# Revised.net
KiCad netlist of a schematic drawn in EAGLE
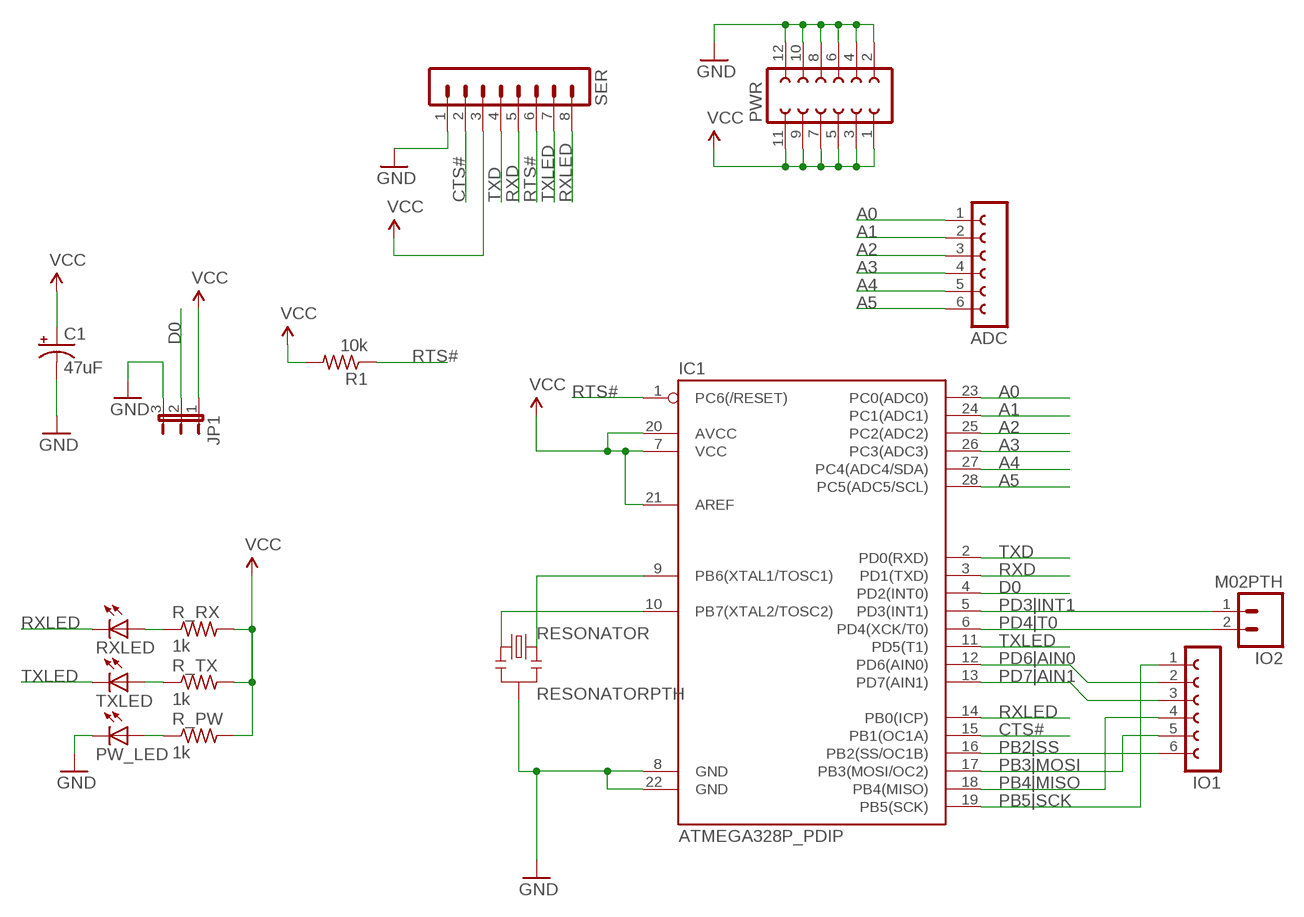
[diagram p0: schematic, sheet 1]

(export (version "E")
  (design (tool "Eeschema 10.0.6"))
  (components
    (comp (ref "ADC")
      (value "FE06-1")
      (footprint "eagle-import:FE06")
      (libsource (lib "eagle-import") (part "FE06-1"))
    )
    (comp (ref "C1")
      (value "47uF")
      (footprint "eagle-import:E2,5-6E")
      (libsource (lib "eagle-import") (part "CPOL-USE2,5-6E"))
    )
    (comp (ref "IC1")
      (value "ATMEGA328P_PDIP")
      (footprint "eagle-import:DIL28-3")
      (libsource (lib "eagle-import") (part "ATMEGA328P_PDIP"))
    )
    (comp (ref "IO1")
      (value "FE06-1")
      (footprint "eagle-import:FE06")
      (libsource (lib "eagle-import") (part "FE06-1"))
    )
    (comp (ref "IO2")
      (value "M02PTH")
      (footprint "eagle-import:1X02")
      (libsource (lib "eagle-import") (part "M02PTH"))
    )
    (comp (ref "JP1")
      (value "JP2E")
      (footprint "eagle-import:JP2")
      (libsource (lib "eagle-import") (part "JP2E"))
    )
    (comp (ref "PWR")
      (value "FE06-2")
      (footprint "eagle-import:FE06-2")
      (libsource (lib "eagle-import") (part "FE06-2"))
    )
    (comp (ref "PW_LED")
      (value "LED5MM")
      (footprint "eagle-import:LED5MM")
      (libsource (lib "eagle-import") (part "LED5MM"))
    )
    (comp (ref "R1")
      (value "10k")
      (footprint "eagle-import:R0805")
      (libsource (lib "eagle-import") (part "R-US_R0805"))
    )
    (comp (ref "RESONATOR")
      (value "RESONATORPTH")
      (footprint "eagle-import:RESONATOR-PTH")
      (libsource (lib "eagle-import") (part "RESONATORPTH"))
    )
    (comp (ref "RXLED")
      (value "LED5MM")
      (footprint "eagle-import:LED5MM")
      (libsource (lib "eagle-import") (part "LED5MM"))
    )
    (comp (ref "R_PW")
      (value "1k")
      (footprint "eagle-import:R0805")
      (libsource (lib "eagle-import") (part "R-US_R0805"))
    )
    (comp (ref "R_RX")
      (value "1k")
      (footprint "eagle-import:R0805")
      (libsource (lib "eagle-import") (part "R-US_R0805"))
    )
    (comp (ref "R_TX")
      (value "1k")
      (footprint "eagle-import:R0805")
      (libsource (lib "eagle-import") (part "R-US_R0805"))
    )
    (comp (ref "SER")
      (value "MA08-1W")
      (footprint "eagle-import:MA08-1W")
      (libsource (lib "eagle-import") (part "MA08-1W"))
    )
    (comp (ref "TXLED")
      (value "LED5MM")
      (footprint "eagle-import:LED5MM")
      (libsource (lib "eagle-import") (part "LED5MM"))
    )
  )
  (nets
    (net (code "1") (name "/A0") (class "Default")
      (node (ref "ADC") (pin "1") (pinfunction "1_1") (pintype "passive"))
      (node (ref "IC1") (pin "23") (pinfunction "PC0(ADC0)_23") (pintype "bidirectional"))
    )
    (net (code "2") (name "/A1") (class "Default")
      (node (ref "ADC") (pin "2") (pinfunction "2_2") (pintype "passive"))
      (node (ref "IC1") (pin "24") (pinfunction "PC1(ADC1)_24") (pintype "bidirectional"))
    )
    (net (code "3") (name "/A2") (class "Default")
      (node (ref "ADC") (pin "3") (pinfunction "3_3") (pintype "passive"))
      (node (ref "IC1") (pin "25") (pinfunction "PC2(ADC2)_25") (pintype "bidirectional"))
    )
    (net (code "4") (name "/A3") (class "Default")
      (node (ref "ADC") (pin "4") (pinfunction "4_4") (pintype "passive"))
      (node (ref "IC1") (pin "26") (pinfunction "PC3(ADC3)_26") (pintype "bidirectional"))
    )
    (net (code "5") (name "/A4") (class "Default")
      (node (ref "ADC") (pin "5") (pinfunction "5_5") (pintype "passive"))
      (node (ref "IC1") (pin "27") (pinfunction "PC4(ADC4/SDA)_27") (pintype "bidirectional"))
    )
    (net (code "6") (name "/A5") (class "Default")
      (node (ref "ADC") (pin "6") (pinfunction "6_6") (pintype "passive"))
      (node (ref "IC1") (pin "28") (pinfunction "PC5(ADC5/SCL)_28") (pintype "bidirectional"))
    )
    (net (code "7") (name "/CTS#") (class "Default")
      (node (ref "IC1") (pin "15") (pinfunction "PB1(OC1A)_15") (pintype "bidirectional"))
      (node (ref "SER") (pin "2") (pinfunction "2_2") (pintype "passive"))
    )
    (net (code "8") (name "/D0") (class "Default")
      (node (ref "IC1") (pin "4") (pinfunction "PD2(INT0)_4") (pintype "bidirectional"))
      (node (ref "JP1") (pin "2") (pinfunction "2_2") (pintype "passive"))
    )
    (net (code "9") (name "/PB2|SS") (class "Default")
      (node (ref "IC1") (pin "16") (pinfunction "PB2(SS/OC1B)_16") (pintype "bidirectional"))
      (node (ref "IO1") (pin "6") (pinfunction "6_6") (pintype "passive"))
    )
    (net (code "10") (name "/PB3|MOSI") (class "Default")
      (node (ref "IC1") (pin "17") (pinfunction "PB3(MOSI/OC2)_17") (pintype "bidirectional"))
      (node (ref "IO1") (pin "5") (pinfunction "5_5") (pintype "passive"))
    )
    (net (code "11") (name "/PB4|MISO") (class "Default")
      (node (ref "IC1") (pin "18") (pinfunction "PB4(MISO)_18") (pintype "bidirectional"))
      (node (ref "IO1") (pin "4") (pinfunction "4_4") (pintype "passive"))
    )
    (net (code "12") (name "/PB5|SCK") (class "Default")
      (node (ref "IC1") (pin "19") (pinfunction "PB5(SCK)_19") (pintype "bidirectional"))
      (node (ref "IO1") (pin "1") (pinfunction "1_1") (pintype "passive"))
    )
    (net (code "13") (name "/PD3|INT1") (class "Default")
      (node (ref "IC1") (pin "5") (pinfunction "PD3(INT1)_5") (pintype "bidirectional"))
      (node (ref "IO2") (pin "1") (pinfunction "1_1") (pintype "passive"))
    )
    (net (code "14") (name "/PD4|T0") (class "Default")
      (node (ref "IC1") (pin "6") (pinfunction "PD4(XCK/T0)_6") (pintype "bidirectional"))
      (node (ref "IO2") (pin "2") (pinfunction "2_2") (pintype "passive"))
    )
    (net (code "15") (name "/PD6|AIN0") (class "Default")
      (node (ref "IC1") (pin "12") (pinfunction "PD6(AIN0)_12") (pintype "bidirectional"))
      (node (ref "IO1") (pin "2") (pinfunction "2_2") (pintype "passive"))
    )
    (net (code "16") (name "/PD7|AIN1") (class "Default")
      (node (ref "IC1") (pin "13") (pinfunction "PD7(AIN1)_13") (pintype "bidirectional"))
      (node (ref "IO1") (pin "3") (pinfunction "3_3") (pintype "passive"))
    )
    (net (code "17") (name "/RTS#") (class "Default")
      (node (ref "IC1") (pin "1") (pinfunction "PC6(/RESET)_1") (pintype "bidirectional"))
      (node (ref "R1") (pin "1") (pinfunction "1_1") (pintype "passive"))
      (node (ref "SER") (pin "6") (pinfunction "6_6") (pintype "passive"))
    )
    (net (code "18") (name "/RXD") (class "Default")
      (node (ref "IC1") (pin "3") (pinfunction "PD1(TXD)_3") (pintype "bidirectional"))
      (node (ref "SER") (pin "5") (pinfunction "5_5") (pintype "passive"))
    )
    (net (code "19") (name "/RXLED") (class "Default")
      (node (ref "IC1") (pin "14") (pinfunction "PB0(ICP)_14") (pintype "bidirectional"))
      (node (ref "RXLED") (pin "K") (pinfunction "C_K") (pintype "passive"))
      (node (ref "SER") (pin "8") (pinfunction "8_8") (pintype "passive"))
    )
    (net (code "20") (name "/TXD") (class "Default")
      (node (ref "IC1") (pin "2") (pinfunction "PD0(RXD)_2") (pintype "bidirectional"))
      (node (ref "SER") (pin "4") (pinfunction "4_4") (pintype "passive"))
    )
    (net (code "21") (name "/TXLED") (class "Default")
      (node (ref "IC1") (pin "11") (pinfunction "PD5(T1)_11") (pintype "bidirectional"))
      (node (ref "SER") (pin "7") (pinfunction "7_7") (pintype "passive"))
      (node (ref "TXLED") (pin "K") (pinfunction "C_K") (pintype "passive"))
    )
    (net (code "22") (name "GND") (class "Default")
      (node (ref "C1") (pin "-") (pinfunction "-_-") (pintype "passive"))
      (node (ref "IC1") (pin "22") (pinfunction "GND_22") (pintype "bidirectional"))
      (node (ref "IC1") (pin "8") (pinfunction "GND_8") (pintype "bidirectional"))
      (node (ref "JP1") (pin "3") (pinfunction "3_3") (pintype "passive"))
      (node (ref "PWR") (pin "10") (pinfunction "10_10") (pintype "passive"))
      (node (ref "PWR") (pin "12") (pinfunction "12_12") (pintype "passive"))
      (node (ref "PWR") (pin "2") (pinfunction "2_2") (pintype "passive"))
      (node (ref "PWR") (pin "4") (pinfunction "4_4") (pintype "passive"))
      (node (ref "PWR") (pin "6") (pinfunction "6_6") (pintype "passive"))
      (node (ref "PWR") (pin "8") (pinfunction "8_8") (pintype "passive"))
      (node (ref "PW_LED") (pin "K") (pinfunction "C_K") (pintype "passive"))
      (node (ref "RESONATOR") (pin "2") (pinfunction "2_2") (pintype "passive"))
      (node (ref "SER") (pin "1") (pinfunction "1_1") (pintype "passive"))
    )
    (net (code "23") (name "Net-(IC1-PB6(XTAL1{slash}TOSC1))") (class "Default")
      (node (ref "IC1") (pin "9") (pinfunction "PB6(XTAL1/TOSC1)_9") (pintype "bidirectional"))
      (node (ref "RESONATOR") (pin "3") (pinfunction "3_3") (pintype "passive"))
    )
    (net (code "24") (name "Net-(IC1-PB7(XTAL2{slash}TOSC2))") (class "Default")
      (node (ref "IC1") (pin "10") (pinfunction "PB7(XTAL2/TOSC2)_10") (pintype "bidirectional"))
      (node (ref "RESONATOR") (pin "1") (pinfunction "1_1") (pintype "passive"))
    )
    (net (code "25") (name "Net-(PW_LED-PadA)") (class "Default")
      (node (ref "PW_LED") (pin "A") (pinfunction "A_A") (pintype "passive"))
      (node (ref "R_PW") (pin "1") (pinfunction "1_1") (pintype "passive"))
    )
    (net (code "26") (name "Net-(RXLED-PadA)") (class "Default")
      (node (ref "RXLED") (pin "A") (pinfunction "A_A") (pintype "passive"))
      (node (ref "R_RX") (pin "1") (pinfunction "1_1") (pintype "passive"))
    )
    (net (code "27") (name "Net-(R_TX-Pad1)") (class "Default")
      (node (ref "R_TX") (pin "1") (pinfunction "1_1") (pintype "passive"))
      (node (ref "TXLED") (pin "A") (pinfunction "A_A") (pintype "passive"))
    )
    (net (code "28") (name "VCC") (class "Default")
      (node (ref "C1") (pin "+") (pinfunction "+_+") (pintype "passive"))
      (node (ref "IC1") (pin "20") (pinfunction "AVCC_20") (pintype "bidirectional"))
      (node (ref "IC1") (pin "21") (pinfunction "AREF_21") (pintype "bidirectional"))
      (node (ref "IC1") (pin "7") (pinfunction "VCC_7") (pintype "bidirectional"))
      (node (ref "JP1") (pin "1") (pinfunction "1_1") (pintype "passive"))
      (node (ref "PWR") (pin "1") (pinfunction "1_1") (pintype "passive"))
      (node (ref "PWR") (pin "11") (pinfunction "11_11") (pintype "passive"))
      (node (ref "PWR") (pin "3") (pinfunction "3_3") (pintype "passive"))
      (node (ref "PWR") (pin "5") (pinfunction "5_5") (pintype "passive"))
      (node (ref "PWR") (pin "7") (pinfunction "7_7") (pintype "passive"))
      (node (ref "PWR") (pin "9") (pinfunction "9_9") (pintype "passive"))
      (node (ref "R1") (pin "2") (pinfunction "2_2") (pintype "passive"))
      (node (ref "R_PW") (pin "2") (pinfunction "2_2") (pintype "passive"))
      (node (ref "R_RX") (pin "2") (pinfunction "2_2") (pintype "passive"))
      (node (ref "R_TX") (pin "2") (pinfunction "2_2") (pintype "passive"))
      (node (ref "SER") (pin "3") (pinfunction "3_3") (pintype "passive"))
    )
  )
)
